# cyu1sheet.net
KiCad netlist of a schematic drawn in Altium Designer
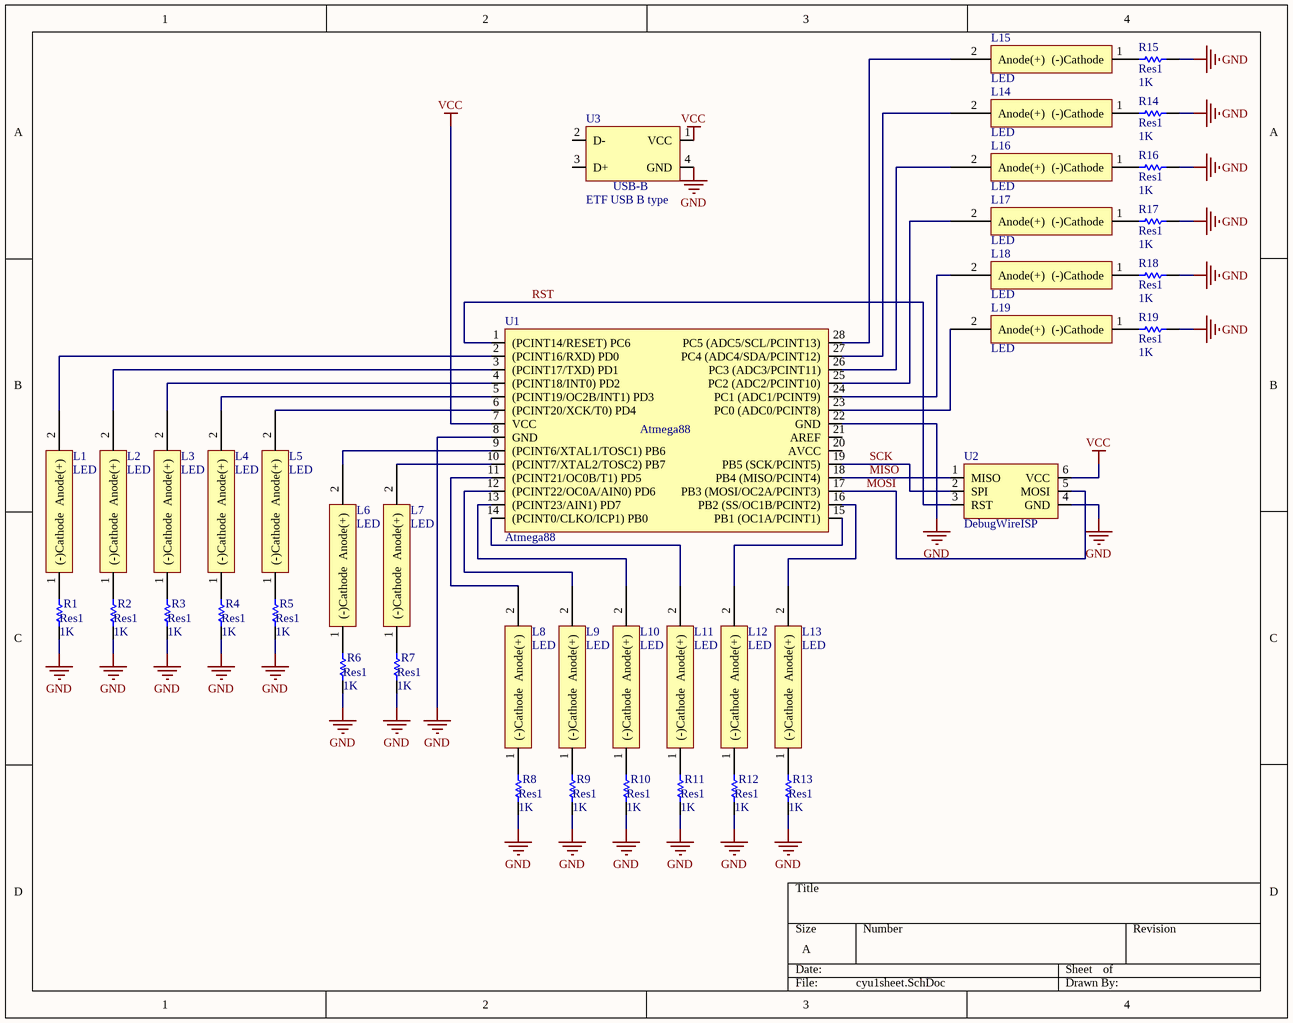
[diagram p0: cyu1sheet.SchDoc]

(export (version "E")
  (design (tool "Eeschema 10.0.6"))
  (components
    (comp (ref "L1") (value "LED") (footprint "LEDth") (libsource (lib "") (part "LEDth_1")))
    (comp (ref "L2") (value "LED") (footprint "LEDth") (libsource (lib "") (part "LEDth_1")))
    (comp (ref "L3") (value "LED") (footprint "LEDth") (libsource (lib "") (part "LEDth_1")))
    (comp (ref "L4") (value "LED") (footprint "LEDth") (libsource (lib "") (part "LEDth_1")))
    (comp (ref "L5") (value "LED") (footprint "LEDth") (libsource (lib "") (part "LEDth_1")))
    (comp (ref "L6") (value "LED") (footprint "LEDth") (libsource (lib "") (part "LEDth_1")))
    (comp (ref "L7") (value "LED") (footprint "LEDth") (libsource (lib "") (part "LEDth_1")))
    (comp (ref "L8") (value "LED") (footprint "LEDth") (libsource (lib "") (part "LEDth_1")))
    (comp (ref "L9") (value "LED") (footprint "LEDth") (libsource (lib "") (part "LEDth_1")))
    (comp (ref "L10") (value "LED") (footprint "LEDth") (libsource (lib "") (part "LEDth_1")))
    (comp (ref "L11") (value "LED") (footprint "LEDth") (libsource (lib "") (part "LEDth_1")))
    (comp (ref "L12") (value "LED") (footprint "LEDth") (libsource (lib "") (part "LEDth_1")))
    (comp (ref "L13") (value "LED") (footprint "LEDth") (libsource (lib "") (part "LEDth_1")))
    (comp (ref "L14")
      (value "LED")
      (footprint "LEDth")
      (libsource (lib "myIntegratedLibrary1") (part "LEDth"))
    )
    (comp (ref "L15")
      (value "LED")
      (footprint "LEDth")
      (libsource (lib "myIntegratedLibrary1") (part "LEDth"))
    )
    (comp (ref "L16")
      (value "LED")
      (footprint "LEDth")
      (libsource (lib "myIntegratedLibrary1") (part "LEDth"))
    )
    (comp (ref "L17")
      (value "LED")
      (footprint "LEDth")
      (libsource (lib "myIntegratedLibrary1") (part "LEDth"))
    )
    (comp (ref "L18")
      (value "LED")
      (footprint "LEDth")
      (libsource (lib "myIntegratedLibrary1") (part "LEDth"))
    )
    (comp (ref "L19")
      (value "LED")
      (footprint "LEDth")
      (libsource (lib "myIntegratedLibrary1") (part "LEDth"))
    )
    (comp (ref "R1")
      (value "Res1")
      (footprint "AXIAL-0.3")
      (description "Resistor")
      (fields (field (name "ALTIUM_VALUE") "1K") (field (name "PUBLISHER") "Altium Limited"))
      (libsource (lib "Miscellaneous Devices") (part "Res1"))
    )
    (comp (ref "R2")
      (value "Res1")
      (footprint "AXIAL-0.3")
      (description "Resistor")
      (fields (field (name "ALTIUM_VALUE") "1K") (field (name "PUBLISHER") "Altium Limited"))
      (libsource (lib "Miscellaneous Devices") (part "Res1"))
    )
    (comp (ref "R3")
      (value "Res1")
      (footprint "AXIAL-0.3")
      (description "Resistor")
      (fields (field (name "ALTIUM_VALUE") "1K") (field (name "PUBLISHER") "Altium Limited"))
      (libsource (lib "Miscellaneous Devices") (part "Res1"))
    )
    (comp (ref "R4")
      (value "Res1")
      (footprint "AXIAL-0.3")
      (description "Resistor")
      (fields (field (name "ALTIUM_VALUE") "1K") (field (name "PUBLISHER") "Altium Limited"))
      (libsource (lib "Miscellaneous Devices") (part "Res1"))
    )
    (comp (ref "R5")
      (value "Res1")
      (footprint "AXIAL-0.3")
      (description "Resistor")
      (fields (field (name "ALTIUM_VALUE") "1K") (field (name "PUBLISHER") "Altium Limited"))
      (libsource (lib "Miscellaneous Devices") (part "Res1"))
    )
    (comp (ref "R6")
      (value "Res1")
      (footprint "AXIAL-0.3")
      (description "Resistor")
      (fields (field (name "ALTIUM_VALUE") "1K") (field (name "PUBLISHER") "Altium Limited"))
      (libsource (lib "Miscellaneous Devices") (part "Res1"))
    )
    (comp (ref "R7")
      (value "Res1")
      (footprint "AXIAL-0.3")
      (description "Resistor")
      (fields (field (name "ALTIUM_VALUE") "1K") (field (name "PUBLISHER") "Altium Limited"))
      (libsource (lib "Miscellaneous Devices") (part "Res1"))
    )
    (comp (ref "R8")
      (value "Res1")
      (footprint "AXIAL-0.3")
      (description "Resistor")
      (fields (field (name "ALTIUM_VALUE") "1K") (field (name "PUBLISHER") "Altium Limited"))
      (libsource (lib "Miscellaneous Devices") (part "Res1"))
    )
    (comp (ref "R9")
      (value "Res1")
      (footprint "AXIAL-0.3")
      (description "Resistor")
      (fields (field (name "ALTIUM_VALUE") "1K") (field (name "PUBLISHER") "Altium Limited"))
      (libsource (lib "Miscellaneous Devices") (part "Res1"))
    )
    (comp (ref "R10")
      (value "Res1")
      (footprint "AXIAL-0.3")
      (description "Resistor")
      (fields (field (name "ALTIUM_VALUE") "1K") (field (name "PUBLISHER") "Altium Limited"))
      (libsource (lib "Miscellaneous Devices") (part "Res1"))
    )
    (comp (ref "R11")
      (value "Res1")
      (footprint "AXIAL-0.3")
      (description "Resistor")
      (fields (field (name "ALTIUM_VALUE") "1K") (field (name "PUBLISHER") "Altium Limited"))
      (libsource (lib "Miscellaneous Devices") (part "Res1"))
    )
    (comp (ref "R12")
      (value "Res1")
      (footprint "AXIAL-0.3")
      (description "Resistor")
      (fields (field (name "ALTIUM_VALUE") "1K") (field (name "PUBLISHER") "Altium Limited"))
      (libsource (lib "Miscellaneous Devices") (part "Res1"))
    )
    (comp (ref "R13")
      (value "Res1")
      (footprint "AXIAL-0.3")
      (description "Resistor")
      (fields (field (name "ALTIUM_VALUE") "1K") (field (name "PUBLISHER") "Altium Limited"))
      (libsource (lib "Miscellaneous Devices") (part "Res1"))
    )
    (comp (ref "R14")
      (value "Res1")
      (footprint "AXIAL-0.3")
      (description "Resistor")
      (fields (field (name "ALTIUM_VALUE") "1K") (field (name "PUBLISHER") "Altium Limited"))
      (libsource (lib "Miscellaneous Devices") (part "Res1"))
    )
    (comp (ref "R15")
      (value "Res1")
      (footprint "AXIAL-0.3")
      (description "Resistor")
      (fields (field (name "ALTIUM_VALUE") "1K") (field (name "PUBLISHER") "Altium Limited"))
      (libsource (lib "Miscellaneous Devices") (part "Res1"))
    )
    (comp (ref "R16")
      (value "Res1")
      (footprint "AXIAL-0.3")
      (description "Resistor")
      (fields (field (name "ALTIUM_VALUE") "1K") (field (name "PUBLISHER") "Altium Limited"))
      (libsource (lib "Miscellaneous Devices") (part "Res1"))
    )
    (comp (ref "R17")
      (value "Res1")
      (footprint "AXIAL-0.3")
      (description "Resistor")
      (fields (field (name "ALTIUM_VALUE") "1K") (field (name "PUBLISHER") "Altium Limited"))
      (libsource (lib "Miscellaneous Devices") (part "Res1"))
    )
    (comp (ref "R18")
      (value "Res1")
      (footprint "AXIAL-0.3")
      (description "Resistor")
      (fields (field (name "ALTIUM_VALUE") "1K") (field (name "PUBLISHER") "Altium Limited"))
      (libsource (lib "Miscellaneous Devices") (part "Res1"))
    )
    (comp (ref "R19")
      (value "Res1")
      (footprint "AXIAL-0.3")
      (description "Resistor")
      (fields (field (name "ALTIUM_VALUE") "1K") (field (name "PUBLISHER") "Altium Limited"))
      (libsource (lib "Miscellaneous Devices") (part "Res1"))
    )
    (comp (ref "U1")
      (value "Atmega88")
      (footprint "ATMEGA328")
      (libsource (lib "myIntegratedLibrary1") (part "Atmega88"))
    )
    (comp (ref "U2")
      (value "DebugWireISP")
      (footprint "6x2pinheader")
      (libsource (lib "myIntegratedLibrary1") (part "DebugWireISP"))
    )
    (comp (ref "U3")
      (value "ETF USB B type")
      (footprint "USB-B")
      (libsource (lib "myIntegratedLibrary1") (part "USB-B"))
    )
  )
  (nets
    (net (code "1") (name "/MISO") (class "Default")
      (node (ref "U1") (pin "18") (pinfunction "PB4_(MISO/PCINT4)_18") (pintype "passive"))
      (node (ref "U2") (pin "1") (pinfunction "MISO_1") (pintype "passive"))
    )
    (net (code "2") (name "/MOSI") (class "Default")
      (node (ref "U1") (pin "17") (pinfunction "PB3_(MOSI/OC2A/PCINT3)_17") (pintype "passive"))
      (node (ref "U2") (pin "5") (pinfunction "MOSI_5") (pintype "passive"))
    )
    (net (code "3") (name "/RST") (class "Default")
      (node (ref "U1") (pin "1") (pinfunction "(PCINT14/RESET)_PC6_1") (pintype "passive"))
      (node (ref "U2") (pin "3") (pinfunction "RST_3") (pintype "passive"))
    )
    (net (code "4") (name "/SCK") (class "Default")
      (node (ref "U1") (pin "19") (pinfunction "PB5_(SCK/PCINT5)_19") (pintype "passive"))
      (node (ref "U2") (pin "2") (pinfunction "SPI_2") (pintype "passive"))
    )
    (net (code "5") (name "GND") (class "Default")
      (node (ref "R1") (pin "1") (pinfunction "1_1") (pintype "passive"))
      (node (ref "R10") (pin "1") (pinfunction "1_1") (pintype "passive"))
      (node (ref "R11") (pin "1") (pinfunction "1_1") (pintype "passive"))
      (node (ref "R12") (pin "1") (pinfunction "1_1") (pintype "passive"))
      (node (ref "R13") (pin "1") (pinfunction "1_1") (pintype "passive"))
      (node (ref "R14") (pin "1") (pinfunction "1_1") (pintype "passive"))
      (node (ref "R15") (pin "1") (pinfunction "1_1") (pintype "passive"))
      (node (ref "R16") (pin "1") (pinfunction "1_1") (pintype "passive"))
      (node (ref "R17") (pin "1") (pinfunction "1_1") (pintype "passive"))
      (node (ref "R18") (pin "1") (pinfunction "1_1") (pintype "passive"))
      (node (ref "R19") (pin "1") (pinfunction "1_1") (pintype "passive"))
      (node (ref "R2") (pin "1") (pinfunction "1_1") (pintype "passive"))
      (node (ref "R3") (pin "1") (pinfunction "1_1") (pintype "passive"))
      (node (ref "R4") (pin "1") (pinfunction "1_1") (pintype "passive"))
      (node (ref "R5") (pin "1") (pinfunction "1_1") (pintype "passive"))
      (node (ref "R6") (pin "1") (pinfunction "1_1") (pintype "passive"))
      (node (ref "R7") (pin "1") (pinfunction "1_1") (pintype "passive"))
      (node (ref "R8") (pin "1") (pinfunction "1_1") (pintype "passive"))
      (node (ref "R9") (pin "1") (pinfunction "1_1") (pintype "passive"))
      (node (ref "U1") (pin "22") (pinfunction "GND_22") (pintype "passive"))
      (node (ref "U1") (pin "8") (pinfunction "GND_8") (pintype "passive"))
      (node (ref "U2") (pin "4") (pinfunction "GND_4") (pintype "passive"))
      (node (ref "U3") (pin "4") (pinfunction "GND_4") (pintype "passive"))
    )
    (net (code "6") (name "Net-(L1-(-)Cathode)") (class "Default")
      (node (ref "L1") (pin "1") (pinfunction "(-)Cathode_1") (pintype "passive"))
      (node (ref "R1") (pin "2") (pinfunction "2_2") (pintype "passive"))
    )
    (net (code "7") (name "Net-(L1-Anode(+))") (class "Default")
      (node (ref "L1") (pin "2") (pinfunction "Anode(+)_2") (pintype "passive"))
      (node (ref "U1") (pin "2") (pinfunction "(PCINT16/RXD)_PD0_2") (pintype "passive"))
    )
    (net (code "8") (name "Net-(L2-(-)Cathode)") (class "Default")
      (node (ref "L2") (pin "1") (pinfunction "(-)Cathode_1") (pintype "passive"))
      (node (ref "R2") (pin "2") (pinfunction "2_2") (pintype "passive"))
    )
    (net (code "9") (name "Net-(L2-Anode(+))") (class "Default")
      (node (ref "L2") (pin "2") (pinfunction "Anode(+)_2") (pintype "passive"))
      (node (ref "U1") (pin "3") (pinfunction "(PCINT17/TXD)_PD1_3") (pintype "passive"))
    )
    (net (code "10") (name "Net-(L3-(-)Cathode)") (class "Default")
      (node (ref "L3") (pin "1") (pinfunction "(-)Cathode_1") (pintype "passive"))
      (node (ref "R3") (pin "2") (pinfunction "2_2") (pintype "passive"))
    )
    (net (code "11") (name "Net-(L3-Anode(+))") (class "Default")
      (node (ref "L3") (pin "2") (pinfunction "Anode(+)_2") (pintype "passive"))
      (node (ref "U1") (pin "4") (pinfunction "(PCINT18/INT0)_PD2_4") (pintype "passive"))
    )
    (net (code "12") (name "Net-(L4-(-)Cathode)") (class "Default")
      (node (ref "L4") (pin "1") (pinfunction "(-)Cathode_1") (pintype "passive"))
      (node (ref "R4") (pin "2") (pinfunction "2_2") (pintype "passive"))
    )
    (net (code "13") (name "Net-(L4-Anode(+))") (class "Default")
      (node (ref "L4") (pin "2") (pinfunction "Anode(+)_2") (pintype "passive"))
      (node (ref "U1") (pin "5") (pinfunction "(PCINT19/OC2B/INT1)_PD3_5") (pintype "passive"))
    )
    (net (code "14") (name "Net-(L5-(-)Cathode)") (class "Default")
      (node (ref "L5") (pin "1") (pinfunction "(-)Cathode_1") (pintype "passive"))
      (node (ref "R5") (pin "2") (pinfunction "2_2") (pintype "passive"))
    )
    (net (code "15") (name "Net-(L5-Anode(+))") (class "Default")
      (node (ref "L5") (pin "2") (pinfunction "Anode(+)_2") (pintype "passive"))
      (node (ref "U1") (pin "6") (pinfunction "(PCINT20/XCK/T0)_PD4_6") (pintype "passive"))
    )
    (net (code "16") (name "Net-(L6-(-)Cathode)") (class "Default")
      (node (ref "L6") (pin "1") (pinfunction "(-)Cathode_1") (pintype "passive"))
      (node (ref "R6") (pin "2") (pinfunction "2_2") (pintype "passive"))
    )
    (net (code "17") (name "Net-(L6-Anode(+))") (class "Default")
      (node (ref "L6") (pin "2") (pinfunction "Anode(+)_2") (pintype "passive"))
      (node (ref "U1") (pin "9") (pinfunction "(PCINT6/XTAL1/TOSC1)_PB6_9") (pintype "passive"))
    )
    (net (code "18") (name "Net-(L7-(-)Cathode)") (class "Default")
      (node (ref "L7") (pin "1") (pinfunction "(-)Cathode_1") (pintype "passive"))
      (node (ref "R7") (pin "2") (pinfunction "2_2") (pintype "passive"))
    )
    (net (code "19") (name "Net-(L7-Anode(+))") (class "Default")
      (node (ref "L7") (pin "2") (pinfunction "Anode(+)_2") (pintype "passive"))
      (node (ref "U1") (pin "10") (pinfunction "(PCINT7/XTAL2/TOSC2)_PB7_10") (pintype "passive"))
    )
    (net (code "20") (name "Net-(L8-(-)Cathode)") (class "Default")
      (node (ref "L8") (pin "1") (pinfunction "(-)Cathode_1") (pintype "passive"))
      (node (ref "R8") (pin "2") (pinfunction "2_2") (pintype "passive"))
    )
    (net (code "21") (name "Net-(L8-Anode(+))") (class "Default")
      (node (ref "L8") (pin "2") (pinfunction "Anode(+)_2") (pintype "passive"))
      (node (ref "U1") (pin "11") (pinfunction "(PCINT21/OC0B/T1)_PD5_11") (pintype "passive"))
    )
    (net (code "22") (name "Net-(L9-(-)Cathode)") (class "Default")
      (node (ref "L9") (pin "1") (pinfunction "(-)Cathode_1") (pintype "passive"))
      (node (ref "R9") (pin "2") (pinfunction "2_2") (pintype "passive"))
    )
    (net (code "23") (name "Net-(L9-Anode(+))") (class "Default")
      (node (ref "L9") (pin "2") (pinfunction "Anode(+)_2") (pintype "passive"))
      (node (ref "U1") (pin "12") (pinfunction "(PCINT22/OC0A/AIN0)_PD6_12") (pintype "passive"))
    )
    (net (code "24") (name "Net-(L10-(-)Cathode)") (class "Default")
      (node (ref "L10") (pin "1") (pinfunction "(-)Cathode_1") (pintype "passive"))
      (node (ref "R10") (pin "2") (pinfunction "2_2") (pintype "passive"))
    )
    (net (code "25") (name "Net-(L10-Anode(+))") (class "Default")
      (node (ref "L10") (pin "2") (pinfunction "Anode(+)_2") (pintype "passive"))
      (node (ref "U1") (pin "13") (pinfunction "(PCINT23/AIN1)_PD7_13") (pintype "passive"))
    )
    (net (code "26") (name "Net-(L11-(-)Cathode)") (class "Default")
      (node (ref "L11") (pin "1") (pinfunction "(-)Cathode_1") (pintype "passive"))
      (node (ref "R11") (pin "2") (pinfunction "2_2") (pintype "passive"))
    )
    (net (code "27") (name "Net-(L11-Anode(+))") (class "Default")
      (node (ref "L11") (pin "2") (pinfunction "Anode(+)_2") (pintype "passive"))
      (node (ref "U1") (pin "14") (pinfunction "(PCINT0/CLKO/ICP1)_PB0_14") (pintype "passive"))
    )
    (net (code "28") (name "Net-(L12-(-)Cathode)") (class "Default")
      (node (ref "L12") (pin "1") (pinfunction "(-)Cathode_1") (pintype "passive"))
      (node (ref "R12") (pin "2") (pinfunction "2_2") (pintype "passive"))
    )
    (net (code "29") (name "Net-(L12-Anode(+))") (class "Default")
      (node (ref "L12") (pin "2") (pinfunction "Anode(+)_2") (pintype "passive"))
      (node (ref "U1") (pin "15") (pinfunction "PB1_(OC1A/PCINT1)_15") (pintype "passive"))
    )
    (net (code "30") (name "Net-(L13-(-)Cathode)") (class "Default")
      (node (ref "L13") (pin "1") (pinfunction "(-)Cathode_1") (pintype "passive"))
      (node (ref "R13") (pin "2") (pinfunction "2_2") (pintype "passive"))
    )
    (net (code "31") (name "Net-(L13-Anode(+))") (class "Default")
      (node (ref "L13") (pin "2") (pinfunction "Anode(+)_2") (pintype "passive"))
      (node (ref "U1") (pin "16") (pinfunction "PB2_(SS/OC1B/PCINT2)_16") (pintype "passive"))
    )
    (net (code "32") (name "Net-(L14-(-)Cathode)") (class "Default")
      (node (ref "L14") (pin "1") (pinfunction "(-)Cathode_1") (pintype "passive"))
      (node (ref "R14") (pin "2") (pinfunction "2_2") (pintype "passive"))
    )
    (net (code "33") (name "Net-(L14-Anode(+))") (class "Default")
      (node (ref "L14") (pin "2") (pinfunction "Anode(+)_2") (pintype "passive"))
      (node (ref "U1") (pin "27") (pinfunction "PC4_(ADC4/SDA/PCINT12)_27") (pintype "passive"))
    )
    (net (code "34") (name "Net-(L15-(-)Cathode)") (class "Default")
      (node (ref "L15") (pin "1") (pinfunction "(-)Cathode_1") (pintype "passive"))
      (node (ref "R15") (pin "2") (pinfunction "2_2") (pintype "passive"))
    )
    (net (code "35") (name "Net-(L15-Anode(+))") (class "Default")
      (node (ref "L15") (pin "2") (pinfunction "Anode(+)_2") (pintype "passive"))
      (node (ref "U1") (pin "28") (pinfunction "PC5_(ADC5/SCL/PCINT13)_28") (pintype "passive"))
    )
    (net (code "36") (name "Net-(L16-(-)Cathode)") (class "Default")
      (node (ref "L16") (pin "1") (pinfunction "(-)Cathode_1") (pintype "passive"))
      (node (ref "R16") (pin "2") (pinfunction "2_2") (pintype "passive"))
    )
    (net (code "37") (name "Net-(L16-Anode(+))") (class "Default")
      (node (ref "L16") (pin "2") (pinfunction "Anode(+)_2") (pintype "passive"))
      (node (ref "U1") (pin "26") (pinfunction "PC3_(ADC3/PCINT11)_26") (pintype "passive"))
    )
    (net (code "38") (name "Net-(L17-(-)Cathode)") (class "Default")
      (node (ref "L17") (pin "1") (pinfunction "(-)Cathode_1") (pintype "passive"))
      (node (ref "R17") (pin "2") (pinfunction "2_2") (pintype "passive"))
    )
    (net (code "39") (name "Net-(L17-Anode(+))") (class "Default")
      (node (ref "L17") (pin "2") (pinfunction "Anode(+)_2") (pintype "passive"))
      (node (ref "U1") (pin "25") (pinfunction "PC2_(ADC2/PCINT10)_25") (pintype "passive"))
    )
    (net (code "40") (name "Net-(L18-(-)Cathode)") (class "Default")
      (node (ref "L18") (pin "1") (pinfunction "(-)Cathode_1") (pintype "passive"))
      (node (ref "R18") (pin "2") (pinfunction "2_2") (pintype "passive"))
    )
    (net (code "41") (name "Net-(L18-Anode(+))") (class "Default")
      (node (ref "L18") (pin "2") (pinfunction "Anode(+)_2") (pintype "passive"))
      (node (ref "U1") (pin "24") (pinfunction "PC1_(ADC1/PCINT9)_24") (pintype "passive"))
    )
    (net (code "42") (name "Net-(L19-(-)Cathode)") (class "Default")
      (node (ref "L19") (pin "1") (pinfunction "(-)Cathode_1") (pintype "passive"))
      (node (ref "R19") (pin "2") (pinfunction "2_2") (pintype "passive"))
    )
    (net (code "43") (name "Net-(L19-Anode(+))") (class "Default")
      (node (ref "L19") (pin "2") (pinfunction "Anode(+)_2") (pintype "passive"))
      (node (ref "U1") (pin "23") (pinfunction "PC0_(ADC0/PCINT8)_23") (pintype "passive"))
    )
    (net (code "44") (name "VCC") (class "Default")
      (node (ref "U1") (pin "7") (pinfunction "VCC_7") (pintype "passive"))
      (node (ref "U2") (pin "6") (pinfunction "VCC_6") (pintype "passive"))
      (node (ref "U3") (pin "1") (pinfunction "VCC_1") (pintype "passive"))
    )
    (net (code "45") (name "unconnected-(U1-AREF-Pad21)") (class "Default")
      (node (ref "U1") (pin "21") (pinfunction "AREF_21") (pintype "passive"))
    )
    (net (code "46") (name "unconnected-(U1-AVCC-Pad20)") (class "Default")
      (node (ref "U1") (pin "20") (pinfunction "AVCC_20") (pintype "passive"))
    )
    (net (code "47") (name "unconnected-(U3-D+-Pad3)") (class "Default")
      (node (ref "U3") (pin "3") (pinfunction "D+_3") (pintype "passive"))
    )
    (net (code "48") (name "unconnected-(U3-D--Pad2)") (class "Default")
      (node (ref "U3") (pin "2") (pinfunction "D-_2") (pintype "passive"))
    )
  )
)
